# Mezzanine.net
KiCad netlist of a schematic drawn in EAGLE
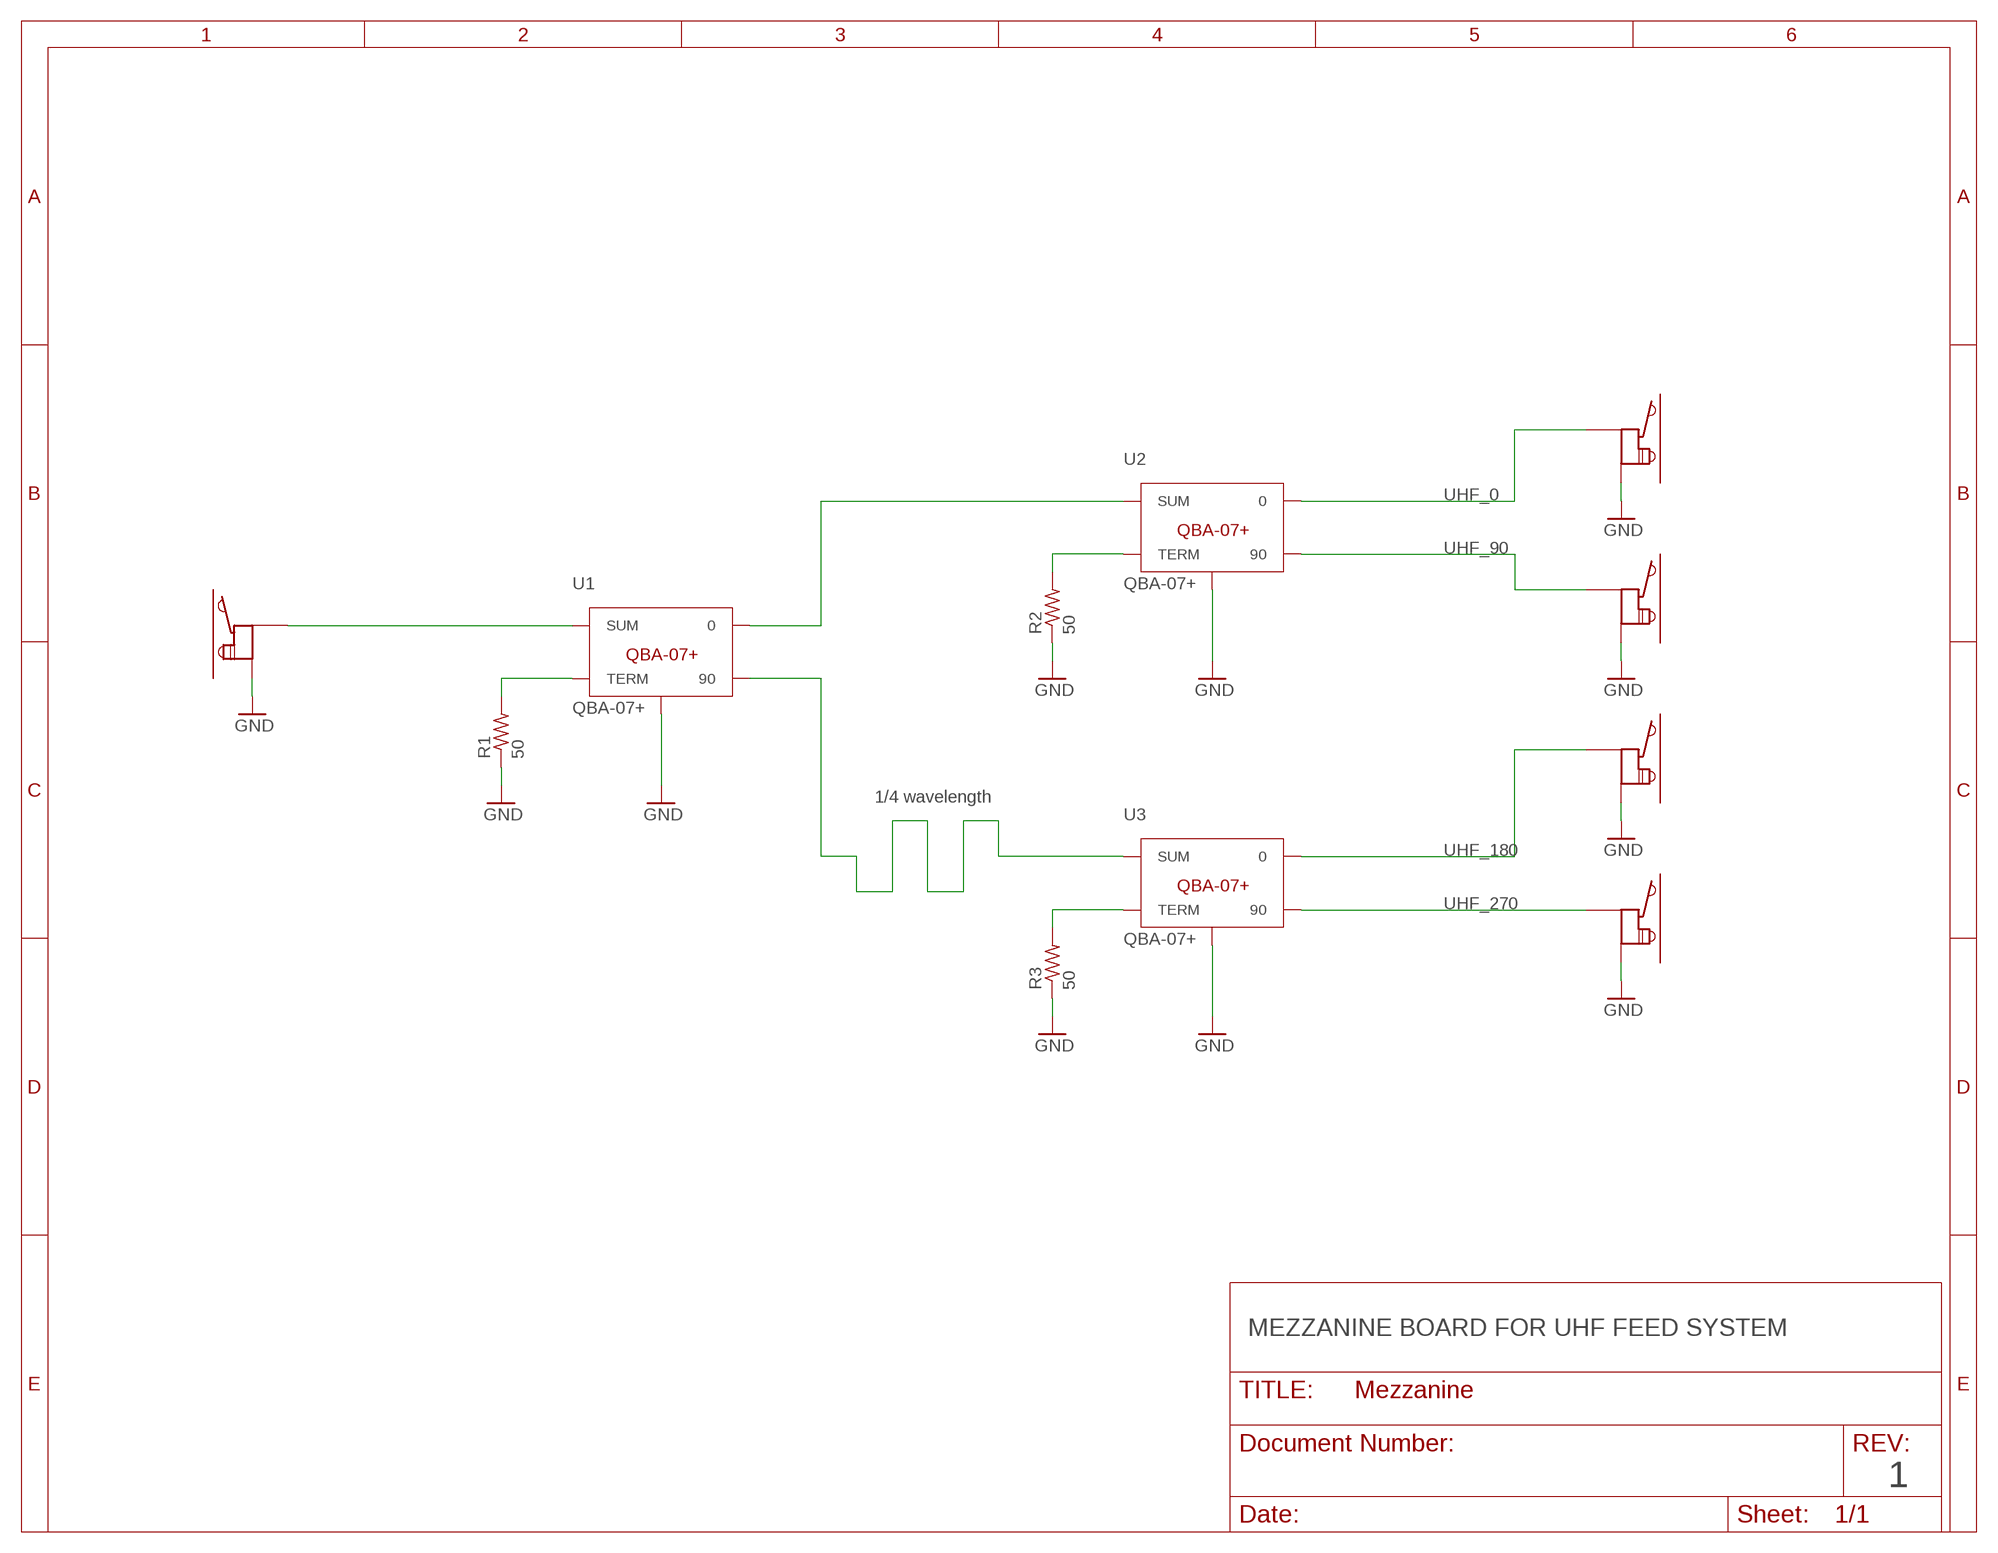
[diagram p0: schematic, sheet 1]

(export (version "E")
  (design (tool "Eeschema 10.0.6"))
  (components
    (comp (ref "R1")
      (value "50")
      (footprint "eagle-import:.0805-B-NOSILK")
      (libsource (lib "eagle-import") (part "R-US_0805-B-NOSILK"))
    )
    (comp (ref "R2")
      (value "50")
      (footprint "eagle-import:.0805-B-NOSILK")
      (libsource (lib "eagle-import") (part "R-US_0805-B-NOSILK"))
    )
    (comp (ref "R3")
      (value "50")
      (footprint "eagle-import:.0805-B-NOSILK")
      (libsource (lib "eagle-import") (part "R-US_0805-B-NOSILK"))
    )
    (comp (ref "U$1")
      (value "R107064070")
      (footprint "eagle-import:R107064070")
      (libsource (lib "eagle-import") (part "R107064070"))
    )
    (comp (ref "U$2")
      (value "R107064070")
      (footprint "eagle-import:R107064070")
      (libsource (lib "eagle-import") (part "R107064070"))
    )
    (comp (ref "U$3")
      (value "R107064070")
      (footprint "eagle-import:R107064070")
      (libsource (lib "eagle-import") (part "R107064070"))
    )
    (comp (ref "U$4")
      (value "R107064070")
      (footprint "eagle-import:R107064070")
      (libsource (lib "eagle-import") (part "R107064070"))
    )
    (comp (ref "U$5")
      (value "R107064070")
      (footprint "eagle-import:R107064070")
      (libsource (lib "eagle-import") (part "R107064070"))
    )
    (comp (ref "U1")
      (value "QBA-07+")
      (footprint "eagle-import:QBA-07+")
      (libsource (lib "eagle-import") (part "QBA-07+"))
    )
    (comp (ref "U2")
      (value "QBA-07+")
      (footprint "eagle-import:QBA-07+")
      (libsource (lib "eagle-import") (part "QBA-07+"))
    )
    (comp (ref "U3")
      (value "QBA-07+")
      (footprint "eagle-import:QBA-07+")
      (libsource (lib "eagle-import") (part "QBA-07+"))
    )
  )
  (nets
    (net (code "1") (name "/UHF_0") (class "Default")
      (node (ref "U$2") (pin "P$1") (pinfunction "P$1_P$1") (pintype "bidirectional"))
      (node (ref "U2") (pin "6") (pinfunction "0_6") (pintype "passive"))
    )
    (net (code "2") (name "/UHF_90") (class "Default")
      (node (ref "U$3") (pin "P$1") (pinfunction "P$1_P$1") (pintype "bidirectional"))
      (node (ref "U2") (pin "10") (pinfunction "90_10") (pintype "passive"))
    )
    (net (code "3") (name "/UHF_180") (class "Default")
      (node (ref "U$4") (pin "P$1") (pinfunction "P$1_P$1") (pintype "bidirectional"))
      (node (ref "U3") (pin "6") (pinfunction "0_6") (pintype "passive"))
    )
    (net (code "4") (name "/UHF_270") (class "Default")
      (node (ref "U$5") (pin "P$1") (pinfunction "P$1_P$1") (pintype "bidirectional"))
      (node (ref "U3") (pin "10") (pinfunction "90_10") (pintype "passive"))
    )
    (net (code "5") (name "GND") (class "Default")
      (node (ref "R1") (pin "1") (pinfunction "1_1") (pintype "passive"))
      (node (ref "R2") (pin "1") (pinfunction "1_1") (pintype "passive"))
      (node (ref "R3") (pin "1") (pinfunction "1_1") (pintype "passive"))
      (node (ref "U$1") (pin "P$2") (pinfunction "P$2_P$2") (pintype "bidirectional"))
      (node (ref "U$1") (pin "P$3") (pinfunction "P$2_P$3") (pintype "bidirectional"))
      (node (ref "U$2") (pin "P$2") (pinfunction "P$2_P$2") (pintype "bidirectional"))
      (node (ref "U$2") (pin "P$3") (pinfunction "P$2_P$3") (pintype "bidirectional"))
      (node (ref "U$3") (pin "P$2") (pinfunction "P$2_P$2") (pintype "bidirectional"))
      (node (ref "U$3") (pin "P$3") (pinfunction "P$2_P$3") (pintype "bidirectional"))
      (node (ref "U$4") (pin "P$2") (pinfunction "P$2_P$2") (pintype "bidirectional"))
      (node (ref "U$4") (pin "P$3") (pinfunction "P$2_P$3") (pintype "bidirectional"))
      (node (ref "U$5") (pin "P$2") (pinfunction "P$2_P$2") (pintype "bidirectional"))
      (node (ref "U$5") (pin "P$3") (pinfunction "P$2_P$3") (pintype "bidirectional"))
      (node (ref "U1") (pin "2") (pinfunction "GND_2") (pintype "power_in"))
      (node (ref "U1") (pin "3") (pinfunction "GND_3") (pintype "power_in"))
      (node (ref "U1") (pin "4") (pinfunction "GND_4") (pintype "power_in"))
      (node (ref "U1") (pin "7") (pinfunction "GND_7") (pintype "power_in"))
      (node (ref "U1") (pin "8") (pinfunction "GND_8") (pintype "power_in"))
      (node (ref "U1") (pin "9") (pinfunction "GND_9") (pintype "power_in"))
      (node (ref "U1") (pin "GND-NO-PAD") (pinfunction "GND_GND-NO-PAD") (pintype "power_in"))
      (node (ref "U2") (pin "2") (pinfunction "GND_2") (pintype "power_in"))
      (node (ref "U2") (pin "3") (pinfunction "GND_3") (pintype "power_in"))
      (node (ref "U2") (pin "4") (pinfunction "GND_4") (pintype "power_in"))
      (node (ref "U2") (pin "7") (pinfunction "GND_7") (pintype "power_in"))
      (node (ref "U2") (pin "8") (pinfunction "GND_8") (pintype "power_in"))
      (node (ref "U2") (pin "9") (pinfunction "GND_9") (pintype "power_in"))
      (node (ref "U2") (pin "GND-NO-PAD") (pinfunction "GND_GND-NO-PAD") (pintype "power_in"))
      (node (ref "U3") (pin "2") (pinfunction "GND_2") (pintype "power_in"))
      (node (ref "U3") (pin "3") (pinfunction "GND_3") (pintype "power_in"))
      (node (ref "U3") (pin "4") (pinfunction "GND_4") (pintype "power_in"))
      (node (ref "U3") (pin "7") (pinfunction "GND_7") (pintype "power_in"))
      (node (ref "U3") (pin "8") (pinfunction "GND_8") (pintype "power_in"))
      (node (ref "U3") (pin "9") (pinfunction "GND_9") (pintype "power_in"))
      (node (ref "U3") (pin "GND-NO-PAD") (pinfunction "GND_GND-NO-PAD") (pintype "power_in"))
    )
    (net (code "6") (name "Net-(U1-0)") (class "Default")
      (node (ref "U1") (pin "6") (pinfunction "0_6") (pintype "passive"))
      (node (ref "U2") (pin "1") (pinfunction "SUM_1") (pintype "passive"))
    )
    (net (code "7") (name "Net-(U1-90)") (class "Default")
      (node (ref "U1") (pin "10") (pinfunction "90_10") (pintype "passive"))
      (node (ref "U3") (pin "1") (pinfunction "SUM_1") (pintype "passive"))
    )
    (net (code "8") (name "Net-(U1-SUM)") (class "Default")
      (node (ref "U$1") (pin "P$1") (pinfunction "P$1_P$1") (pintype "bidirectional"))
      (node (ref "U1") (pin "1") (pinfunction "SUM_1") (pintype "passive"))
    )
    (net (code "9") (name "Net-(U1-TERM)") (class "Default")
      (node (ref "R1") (pin "2") (pinfunction "2_2") (pintype "passive"))
      (node (ref "U1") (pin "5") (pinfunction "TERM_5") (pintype "passive"))
    )
    (net (code "10") (name "Net-(U2-TERM)") (class "Default")
      (node (ref "R2") (pin "2") (pinfunction "2_2") (pintype "passive"))
      (node (ref "U2") (pin "5") (pinfunction "TERM_5") (pintype "passive"))
    )
    (net (code "11") (name "Net-(U3-TERM)") (class "Default")
      (node (ref "R3") (pin "2") (pinfunction "2_2") (pintype "passive"))
      (node (ref "U3") (pin "5") (pinfunction "TERM_5") (pintype "passive"))
    )
  )
)
